# DIO.net
KiCad netlist of a schematic drawn in Altium Designer
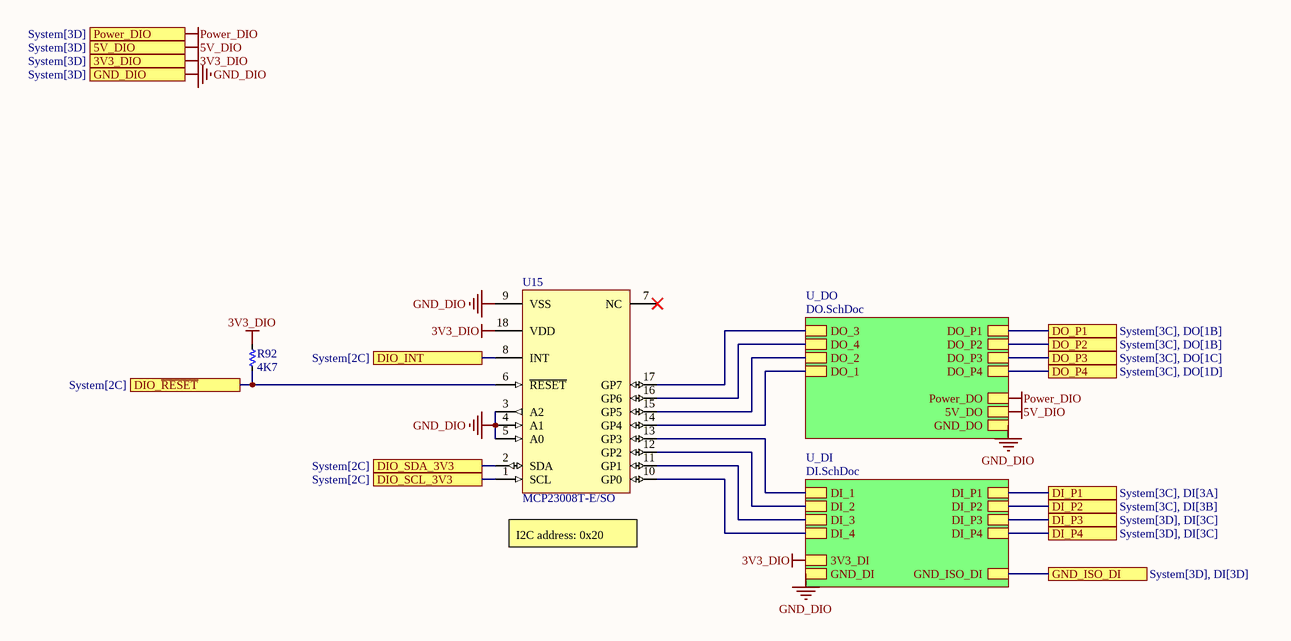
[diagram p0: DIO.SchDoc]

(export (version "E")
  (design (tool "Eeschema 10.0.6"))
  (components
    (comp (ref "R92")
      (value "4K7")
      (footprint "RES-SMD-0603")
      (description "Res 0603 5%")
      (fields
        (field (name "MANUFACTURER") "Generic Components")
        (field (name "PUBLISHER") "Altium Hobart Technology Centre")
      )
      (libsource (lib "TechMT.VN_Lib_Project v2") (part "Res-SMD"))
    )
    (comp (ref "U15")
      (value "MCP23008T-E/SO")
      (footprint "SOIC-SO18_N")
      (description "8-Bit I/O Expander with Serial Interface, 18-Pin SOIC, Extended Temperature, Tape and Reel")
      (libsource (lib "Altium Content Vault") (part "PR-BUSIC-MCP23008-18"))
    )
  )
  (nets
    (net (code "1") (name "/DIO_INT") (class "Default")
      (node (ref "U15") (pin "8") (pinfunction "INT_8") (pintype "open_collector"))
    )
    (net (code "2") (name "/DIO_SCL_3V3") (class "Default")
      (node (ref "U15") (pin "1") (pinfunction "SCL_1") (pintype "input"))
    )
    (net (code "3") (name "/DIO_SDA_3V3") (class "Default")
      (node (ref "U15") (pin "2") (pinfunction "SDA_2") (pintype "bidirectional"))
    )
    (net (code "4") (name "/DIO_~{RESET}") (class "Default")
      (node (ref "R92") (pin "1") (pinfunction "1_1") (pintype "passive"))
      (node (ref "U15") (pin "6") (pinfunction "~{RESET}_6") (pintype "input"))
    )
    (net (code "5") (name "/DI_1") (class "Default")
      (node (ref "U15") (pin "13") (pinfunction "GP3_13") (pintype "bidirectional"))
    )
    (net (code "6") (name "/DI_2") (class "Default")
      (node (ref "U15") (pin "12") (pinfunction "GP2_12") (pintype "bidirectional"))
    )
    (net (code "7") (name "/DI_3") (class "Default")
      (node (ref "U15") (pin "11") (pinfunction "GP1_11") (pintype "bidirectional"))
    )
    (net (code "8") (name "/DI_4") (class "Default")
      (node (ref "U15") (pin "10") (pinfunction "GP0_10") (pintype "bidirectional"))
    )
    (net (code "13") (name "/DO_1") (class "Default")
      (node (ref "U15") (pin "14") (pinfunction "GP4_14") (pintype "bidirectional"))
    )
    (net (code "14") (name "/DO_2") (class "Default")
      (node (ref "U15") (pin "15") (pinfunction "GP5_15") (pintype "bidirectional"))
    )
    (net (code "15") (name "/DO_3") (class "Default")
      (node (ref "U15") (pin "17") (pinfunction "GP7_17") (pintype "bidirectional"))
    )
    (net (code "16") (name "/DO_4") (class "Default")
      (node (ref "U15") (pin "16") (pinfunction "GP6_16") (pintype "bidirectional"))
    )
    (net (code "22") (name "3V3_DIO") (class "Default")
      (node (ref "R92") (pin "2") (pinfunction "2_2") (pintype "passive"))
      (node (ref "U15") (pin "18") (pinfunction "VDD_18") (pintype "power_in"))
    )
    (net (code "24") (name "GND_DIO") (class "Default")
      (node (ref "U15") (pin "3") (pinfunction "A2_3") (pintype "output"))
      (node (ref "U15") (pin "4") (pinfunction "A1_4") (pintype "input"))
      (node (ref "U15") (pin "5") (pinfunction "A0_5") (pintype "input"))
      (node (ref "U15") (pin "9") (pinfunction "VSS_9") (pintype "power_in"))
    )
    (net (code "26") (name "unconnected-(U15-NC-Pad7)") (class "Default")
      (node (ref "U15") (pin "7") (pinfunction "NC_7") (pintype "passive+no_connect"))
    )
  )
)
